# esquem_tico.net
KiCad netlist of a schematic drawn in EAGLE
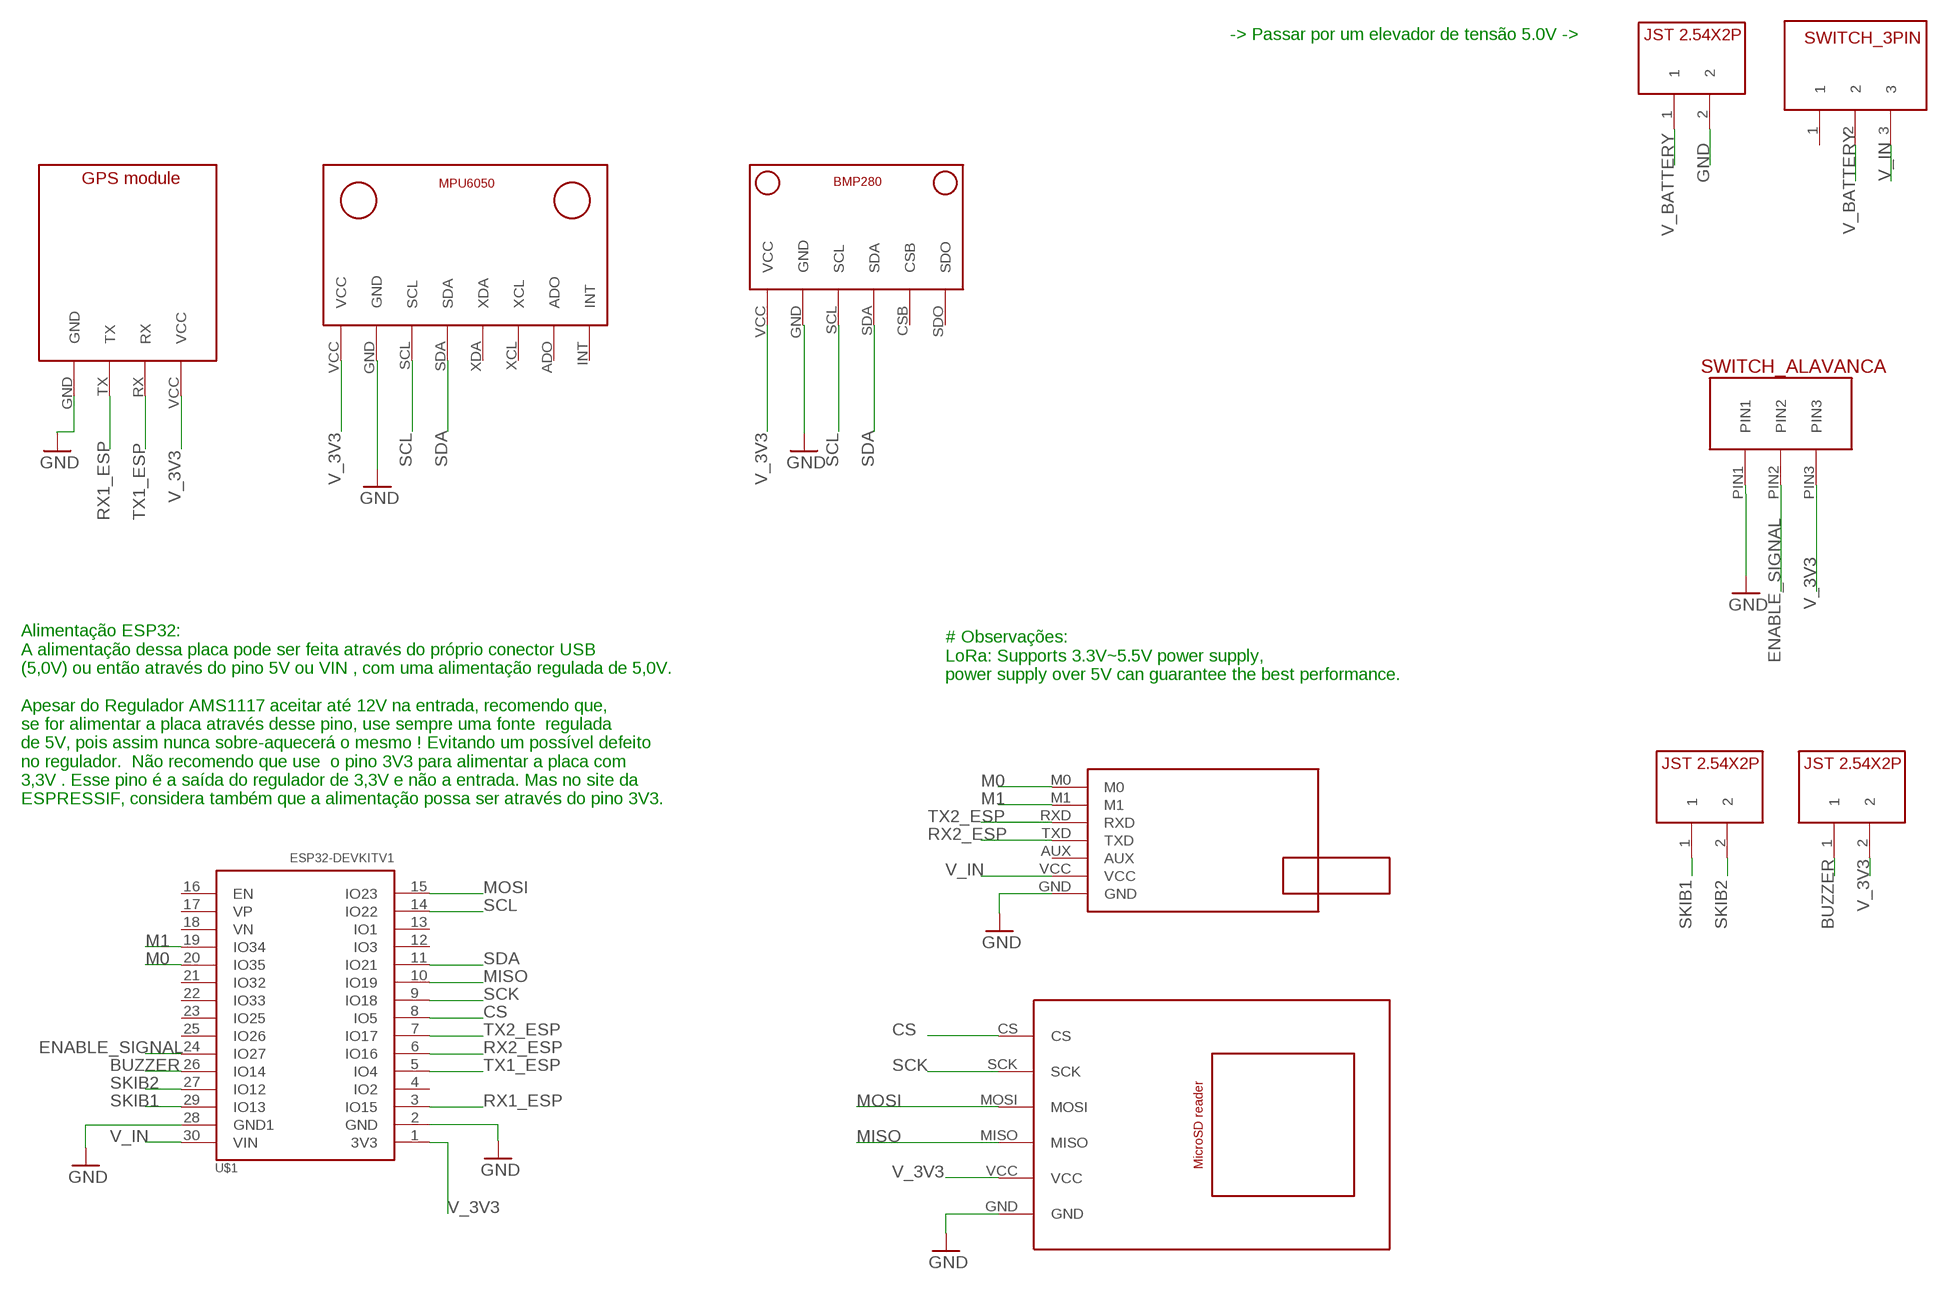
[diagram p0: schematic, sheet 1]

(export (version "E")
  (design (tool "Eeschema 10.0.6"))
  (components
    (comp (ref "U$1")
      (value "ESP32DEVKITV1")
      (footprint "eagle-import:ESP32-DEVKITV1")
      (libsource (lib "eagle-import") (part "ESP32DEVKITV1"))
    )
    (comp (ref "U$2")
      (value "E22-400T30D")
      (footprint "eagle-import:E22-400T30D_FOOTPRINT")
      (libsource (lib "eagle-import") (part "E22-400T30D"))
    )
    (comp (ref "U$3")
      (value "GPS_MODULE")
      (footprint "eagle-import:GPS_MODULE_FOOTPRINT")
      (libsource (lib "eagle-import") (part "GPS_MODULE"))
    )
    (comp (ref "U$4")
      (value "BMP280V1")
      (footprint "eagle-import:BMP280_FOOTPRINT")
      (libsource (lib "eagle-import") (part "BMP280V1"))
    )
    (comp (ref "U$5")
      (value "SWITCH_ALAVANCA")
      (footprint "eagle-import:SWITCH_ALAVANCA_FOOTPRINT")
      (libsource (lib "eagle-import") (part "SWITCH_ALAVANCA"))
    )
    (comp (ref "U$6")
      (value "MPU6050V1")
      (footprint "eagle-import:MPU6050_FOOTPRINT")
      (libsource (lib "eagle-import") (part "MPU6050V1"))
    )
    (comp (ref "U$7")
      (value "MICROSD_READER")
      (footprint "eagle-import:MICROSD_READER_FOOTPRINT")
      (libsource (lib "eagle-import") (part "MICROSD_READER"))
    )
    (comp (ref "U$8")
      (value "JST2.54X2P")
      (footprint "eagle-import:JST2.54X2P_FOOTPRINT")
      (libsource (lib "eagle-import") (part "JST2.54X2P"))
    )
    (comp (ref "U$9")
      (value "JST2.54X2P")
      (footprint "eagle-import:JST2.54X2P_FOOTPRINT")
      (libsource (lib "eagle-import") (part "JST2.54X2P"))
    )
    (comp (ref "U$11")
      (value "SWITCH_3PIN")
      (footprint "eagle-import:SWITCH_3PIN")
      (libsource (lib "eagle-import") (part "SWITCH_3PIN"))
    )
    (comp (ref "U$12")
      (value "JST2.54X2P")
      (footprint "eagle-import:JST2.54X2P_FOOTPRINT")
      (libsource (lib "eagle-import") (part "JST2.54X2P"))
    )
  )
  (nets
    (net (code "1") (name "/BUZZER") (class "Default")
      (node (ref "U$1") (pin "26") (pinfunction "IO14_26") (pintype "bidirectional"))
      (node (ref "U$9") (pin "1") (pinfunction "1_1") (pintype "bidirectional"))
    )
    (net (code "2") (name "/CS") (class "Default")
      (node (ref "U$1") (pin "8") (pinfunction "IO5_8") (pintype "bidirectional"))
      (node (ref "U$7") (pin "CS") (pinfunction "CS_CS") (pintype "bidirectional"))
    )
    (net (code "3") (name "/ENABLE_SIGNAL") (class "Default")
      (node (ref "U$1") (pin "24") (pinfunction "IO27_24") (pintype "bidirectional"))
      (node (ref "U$5") (pin "PIN2") (pinfunction "PIN2_PIN2") (pintype "bidirectional"))
    )
    (net (code "4") (name "/M0") (class "Default")
      (node (ref "U$1") (pin "20") (pinfunction "IO35_20") (pintype "bidirectional"))
      (node (ref "U$2") (pin "M0") (pinfunction "M0_M0") (pintype "bidirectional"))
    )
    (net (code "5") (name "/M1") (class "Default")
      (node (ref "U$1") (pin "19") (pinfunction "IO34_19") (pintype "bidirectional"))
      (node (ref "U$2") (pin "M1") (pinfunction "M1_M1") (pintype "bidirectional"))
    )
    (net (code "6") (name "/MISO") (class "Default")
      (node (ref "U$1") (pin "10") (pinfunction "IO19_10") (pintype "bidirectional"))
      (node (ref "U$7") (pin "MISO") (pinfunction "MISO_MISO") (pintype "bidirectional"))
    )
    (net (code "7") (name "/MOSI") (class "Default")
      (node (ref "U$1") (pin "15") (pinfunction "IO23_15") (pintype "bidirectional"))
      (node (ref "U$7") (pin "MOSI") (pinfunction "MOSI_MOSI") (pintype "bidirectional"))
    )
    (net (code "8") (name "/RX1_ESP") (class "Default")
      (node (ref "U$1") (pin "3") (pinfunction "IO15_3") (pintype "bidirectional"))
      (node (ref "U$3") (pin "TX") (pinfunction "TX_TX") (pintype "bidirectional"))
    )
    (net (code "9") (name "/RX2_ESP") (class "Default")
      (node (ref "U$1") (pin "6") (pinfunction "IO16_6") (pintype "bidirectional"))
      (node (ref "U$2") (pin "TXD") (pinfunction "TXD_TXD") (pintype "bidirectional"))
    )
    (net (code "10") (name "/SCK") (class "Default")
      (node (ref "U$1") (pin "9") (pinfunction "IO18_9") (pintype "bidirectional"))
      (node (ref "U$7") (pin "SCK") (pinfunction "SCK_SCK") (pintype "bidirectional"))
    )
    (net (code "11") (name "/SCL") (class "Default")
      (node (ref "U$1") (pin "14") (pinfunction "IO22_14") (pintype "bidirectional"))
      (node (ref "U$4") (pin "SCL") (pinfunction "SCL_SCL") (pintype "bidirectional"))
      (node (ref "U$6") (pin "SCL") (pinfunction "SCL_SCL") (pintype "bidirectional"))
    )
    (net (code "12") (name "/SDA") (class "Default")
      (node (ref "U$1") (pin "11") (pinfunction "IO21_11") (pintype "bidirectional"))
      (node (ref "U$4") (pin "SDA") (pinfunction "SDA_SDA") (pintype "bidirectional"))
      (node (ref "U$6") (pin "SDA") (pinfunction "SDA_SDA") (pintype "bidirectional"))
    )
    (net (code "13") (name "/SKIB1") (class "Default")
      (node (ref "U$1") (pin "29") (pinfunction "IO13_29") (pintype "bidirectional"))
      (node (ref "U$8") (pin "1") (pinfunction "1_1") (pintype "bidirectional"))
    )
    (net (code "14") (name "/SKIB2") (class "Default")
      (node (ref "U$1") (pin "27") (pinfunction "IO12_27") (pintype "bidirectional"))
      (node (ref "U$8") (pin "2") (pinfunction "2_2") (pintype "bidirectional"))
    )
    (net (code "15") (name "/TX1_ESP") (class "Default")
      (node (ref "U$1") (pin "5") (pinfunction "IO4_5") (pintype "bidirectional"))
      (node (ref "U$3") (pin "RX") (pinfunction "RX_RX") (pintype "bidirectional"))
    )
    (net (code "16") (name "/TX2_ESP") (class "Default")
      (node (ref "U$1") (pin "7") (pinfunction "IO17_7") (pintype "bidirectional"))
      (node (ref "U$2") (pin "RXD") (pinfunction "RXD_RXD") (pintype "bidirectional"))
    )
    (net (code "17") (name "/V_3V3") (class "Default")
      (node (ref "U$1") (pin "1") (pinfunction "3V3_1") (pintype "bidirectional"))
      (node (ref "U$3") (pin "VCC") (pinfunction "VCC_VCC") (pintype "bidirectional"))
      (node (ref "U$4") (pin "VCC") (pinfunction "VCC_VCC") (pintype "bidirectional"))
      (node (ref "U$5") (pin "PIN3") (pinfunction "PIN3_PIN3") (pintype "bidirectional"))
      (node (ref "U$6") (pin "VCC") (pinfunction "VCC_VCC") (pintype "bidirectional"))
      (node (ref "U$7") (pin "VCC") (pinfunction "VCC_VCC") (pintype "bidirectional"))
      (node (ref "U$9") (pin "2") (pinfunction "2_2") (pintype "bidirectional"))
    )
    (net (code "18") (name "/V_BATTERY") (class "Default")
      (node (ref "U$11") (pin "2") (pinfunction "2_2") (pintype "bidirectional"))
      (node (ref "U$12") (pin "1") (pinfunction "1_1") (pintype "bidirectional"))
    )
    (net (code "19") (name "/V_IN") (class "Default")
      (node (ref "U$1") (pin "30") (pinfunction "VIN_30") (pintype "bidirectional"))
      (node (ref "U$11") (pin "3") (pinfunction "3_3") (pintype "bidirectional"))
      (node (ref "U$2") (pin "VCC") (pinfunction "VCC_VCC") (pintype "bidirectional"))
    )
    (net (code "20") (name "GND") (class "Default")
      (node (ref "U$1") (pin "2") (pinfunction "GND_2") (pintype "bidirectional"))
      (node (ref "U$1") (pin "28") (pinfunction "GND1_28") (pintype "bidirectional"))
      (node (ref "U$12") (pin "2") (pinfunction "2_2") (pintype "bidirectional"))
      (node (ref "U$2") (pin "GND") (pinfunction "GND_GND") (pintype "bidirectional"))
      (node (ref "U$3") (pin "GND") (pinfunction "GND_GND") (pintype "bidirectional"))
      (node (ref "U$4") (pin "GND") (pinfunction "GND_GND") (pintype "bidirectional"))
      (node (ref "U$5") (pin "PIN1") (pinfunction "PIN1_PIN1") (pintype "bidirectional"))
      (node (ref "U$6") (pin "GND") (pinfunction "GND_GND") (pintype "bidirectional"))
      (node (ref "U$7") (pin "GND") (pinfunction "GND_GND") (pintype "bidirectional"))
    )
    (net (code "21") (name "unconnected-(U$1-EN-Pad16)") (class "Default")
      (node (ref "U$1") (pin "16") (pinfunction "EN_16") (pintype "bidirectional"))
    )
    (net (code "22") (name "unconnected-(U$1-IO1-Pad13)") (class "Default")
      (node (ref "U$1") (pin "13") (pinfunction "IO1_13") (pintype "bidirectional"))
    )
    (net (code "23") (name "unconnected-(U$1-IO2-Pad4)") (class "Default")
      (node (ref "U$1") (pin "4") (pinfunction "IO2_4") (pintype "bidirectional"))
    )
    (net (code "24") (name "unconnected-(U$1-IO3-Pad12)") (class "Default")
      (node (ref "U$1") (pin "12") (pinfunction "IO3_12") (pintype "bidirectional"))
    )
    (net (code "25") (name "unconnected-(U$1-IO25-Pad23)") (class "Default")
      (node (ref "U$1") (pin "23") (pinfunction "IO25_23") (pintype "bidirectional"))
    )
    (net (code "26") (name "unconnected-(U$1-IO26-Pad25)") (class "Default")
      (node (ref "U$1") (pin "25") (pinfunction "IO26_25") (pintype "bidirectional"))
    )
    (net (code "27") (name "unconnected-(U$1-IO32-Pad21)") (class "Default")
      (node (ref "U$1") (pin "21") (pinfunction "IO32_21") (pintype "bidirectional"))
    )
    (net (code "28") (name "unconnected-(U$1-IO33-Pad22)") (class "Default")
      (node (ref "U$1") (pin "22") (pinfunction "IO33_22") (pintype "bidirectional"))
    )
    (net (code "29") (name "unconnected-(U$1-VN-Pad18)") (class "Default")
      (node (ref "U$1") (pin "18") (pinfunction "VN_18") (pintype "bidirectional"))
    )
    (net (code "30") (name "unconnected-(U$1-VP-Pad17)") (class "Default")
      (node (ref "U$1") (pin "17") (pinfunction "VP_17") (pintype "bidirectional"))
    )
    (net (code "31") (name "unconnected-(U$2-PadAUX)") (class "Default")
      (node (ref "U$2") (pin "AUX") (pinfunction "AUX_AUX") (pintype "bidirectional"))
    )
    (net (code "32") (name "unconnected-(U$4-PadCSB)") (class "Default")
      (node (ref "U$4") (pin "CSB") (pinfunction "CSB_CSB") (pintype "bidirectional"))
    )
    (net (code "33") (name "unconnected-(U$4-PadSDO)") (class "Default")
      (node (ref "U$4") (pin "SDO") (pinfunction "SDO_SDO") (pintype "bidirectional"))
    )
    (net (code "34") (name "unconnected-(U$6-PadADO)") (class "Default")
      (node (ref "U$6") (pin "ADO") (pinfunction "ADO_ADO") (pintype "bidirectional"))
    )
    (net (code "35") (name "unconnected-(U$6-PadINT)") (class "Default")
      (node (ref "U$6") (pin "INT") (pinfunction "INT_INT") (pintype "bidirectional"))
    )
    (net (code "36") (name "unconnected-(U$6-PadXCL)") (class "Default")
      (node (ref "U$6") (pin "XCL") (pinfunction "XCL_XCL") (pintype "bidirectional"))
    )
    (net (code "37") (name "unconnected-(U$6-PadXDA)") (class "Default")
      (node (ref "U$6") (pin "XDA") (pinfunction "XDA_XDA") (pintype "bidirectional"))
    )
    (net (code "38") (name "unconnected-(U$11-Pad1)") (class "Default")
      (node (ref "U$11") (pin "1") (pinfunction "1_1") (pintype "bidirectional"))
    )
  )
)
